# iGlass_Ext_v1.net
KiCad netlist of a schematic drawn in EAGLE
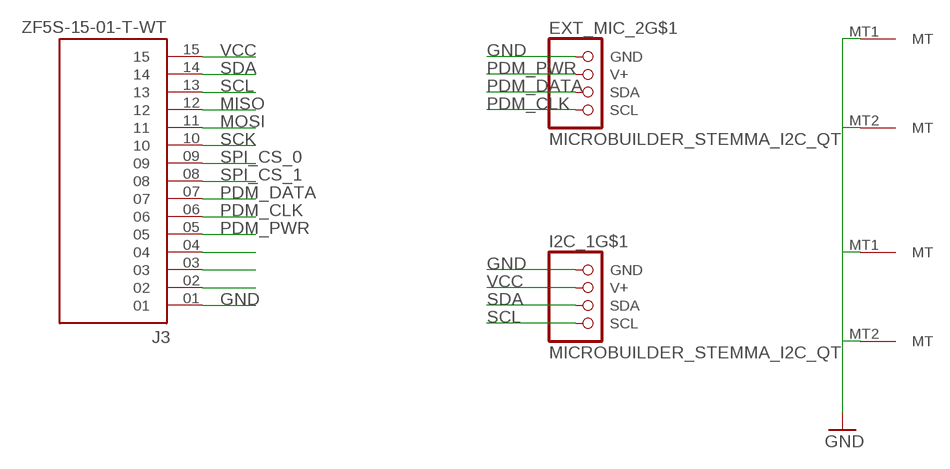
[diagram p0: schematic, sheet 1]

(export (version "E")
  (design (tool "Eeschema 10.0.6"))
  (components
    (comp (ref "EXT_MIC_2")
      (value "MICROBUILDER_STEMMA_I2C_QT")
      (footprint "eagle-import:MICROBUILDER_JST_SH4")
      (libsource (lib "eagle-import") (part "MICROBUILDER_STEMMA_I2C_QT"))
    )
    (comp (ref "I2C_1")
      (value "MICROBUILDER_STEMMA_I2C_QT")
      (footprint "eagle-import:MICROBUILDER_JST_SH4")
      (libsource (lib "eagle-import") (part "MICROBUILDER_STEMMA_I2C_QT"))
    )
    (comp (ref "J3")
      (value "ZF5S-15-01-T-WT")
      (footprint "eagle-import:SAMTEC_ZF5S-15-01-T-WT")
      (fields (field (name "MANUFACTURER") "SAMTEC "))
      (libsource (lib "eagle-import") (part "ZF5S-15-01-T-WT"))
    )
  )
  (nets
    (net (code "1") (name "/MISO") (class "Default")
      (node (ref "J3") (pin "12") (pinfunction "12_12") (pintype "passive"))
    )
    (net (code "2") (name "/MOSI") (class "Default")
      (node (ref "J3") (pin "11") (pinfunction "11_11") (pintype "passive"))
    )
    (net (code "3") (name "/PDM_CLK") (class "Default")
      (node (ref "EXT_MIC_2") (pin "4") (pinfunction "SCL_4") (pintype "passive"))
      (node (ref "J3") (pin "06") (pinfunction "06_06") (pintype "passive"))
    )
    (net (code "4") (name "/PDM_DATA") (class "Default")
      (node (ref "EXT_MIC_2") (pin "3") (pinfunction "SDA_3") (pintype "passive"))
      (node (ref "J3") (pin "07") (pinfunction "07_07") (pintype "passive"))
    )
    (net (code "5") (name "/PDM_PWR") (class "Default")
      (node (ref "EXT_MIC_2") (pin "2") (pinfunction "V+_2") (pintype "passive"))
      (node (ref "J3") (pin "05") (pinfunction "05_05") (pintype "passive"))
    )
    (net (code "6") (name "/SCK") (class "Default")
      (node (ref "J3") (pin "10") (pinfunction "10_10") (pintype "passive"))
    )
    (net (code "7") (name "/SCL") (class "Default")
      (node (ref "I2C_1") (pin "4") (pinfunction "SCL_4") (pintype "passive"))
      (node (ref "J3") (pin "13") (pinfunction "13_13") (pintype "passive"))
    )
    (net (code "8") (name "/SDA") (class "Default")
      (node (ref "I2C_1") (pin "3") (pinfunction "SDA_3") (pintype "passive"))
      (node (ref "J3") (pin "14") (pinfunction "14_14") (pintype "passive"))
    )
    (net (code "9") (name "/SPI_CS_0") (class "Default")
      (node (ref "J3") (pin "09") (pinfunction "09_09") (pintype "passive"))
    )
    (net (code "10") (name "/SPI_CS_1") (class "Default")
      (node (ref "J3") (pin "08") (pinfunction "08_08") (pintype "passive"))
    )
    (net (code "11") (name "/VCC") (class "Default")
      (node (ref "I2C_1") (pin "2") (pinfunction "V+_2") (pintype "passive"))
      (node (ref "J3") (pin "15") (pinfunction "15_15") (pintype "passive"))
    )
    (net (code "12") (name "GND") (class "Default")
      (node (ref "EXT_MIC_2") (pin "1") (pinfunction "GND_1") (pintype "passive"))
      (node (ref "EXT_MIC_2") (pin "MT1") (pinfunction "MT_MT1") (pintype "bidirectional"))
      (node (ref "EXT_MIC_2") (pin "MT2") (pinfunction "MT_MT2") (pintype "bidirectional"))
      (node (ref "I2C_1") (pin "1") (pinfunction "GND_1") (pintype "passive"))
      (node (ref "I2C_1") (pin "MT1") (pinfunction "MT_MT1") (pintype "bidirectional"))
      (node (ref "I2C_1") (pin "MT2") (pinfunction "MT_MT2") (pintype "bidirectional"))
      (node (ref "J3") (pin "01") (pinfunction "01_01") (pintype "passive"))
    )
    (net (code "13") (name "unconnected-(J3-Pad02)") (class "Default")
      (node (ref "J3") (pin "02") (pinfunction "02_02") (pintype "passive"))
    )
    (net (code "14") (name "unconnected-(J3-Pad03)") (class "Default")
      (node (ref "J3") (pin "03") (pinfunction "03_03") (pintype "passive"))
    )
    (net (code "15") (name "unconnected-(J3-Pad04)") (class "Default")
      (node (ref "J3") (pin "04") (pinfunction "04_04") (pintype "passive"))
    )
  )
)
